# PlacaResistencia_VFinal.net
KiCad netlist of a schematic drawn in EAGLE
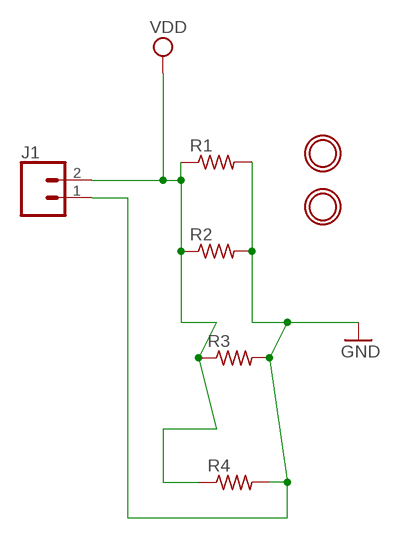
[diagram p0: schematic, sheet 1]

(export (version "E")
  (design (tool "Eeschema 10.0.6"))
  (components
    (comp (ref "GND")
      (value "MOUNTINGHOLE2.5")
      (footprint "eagle-import:MOUNTINGHOLE_2.5_PLATED")
      (libsource (lib "eagle-import") (part "MOUNTINGHOLE2.5"))
    )
    (comp (ref "GND2")
      (value "MOUNTINGHOLE2.5")
      (footprint "eagle-import:MOUNTINGHOLE_2.5_PLATED")
      (libsource (lib "eagle-import") (part "MOUNTINGHOLE2.5"))
    )
    (comp (ref "J1")
      (value "CONN_02")
      (footprint "eagle-import:1X02")
      (libsource (lib "eagle-import") (part "CONN_02"))
    )
    (comp (ref "R1")
      (value "R-US_R2512")
      (footprint "eagle-import:R2512")
      (libsource (lib "eagle-import") (part "R-US_R2512"))
    )
    (comp (ref "R2")
      (value "R-US_R2512")
      (footprint "eagle-import:R2512")
      (libsource (lib "eagle-import") (part "R-US_R2512"))
    )
    (comp (ref "R3")
      (value "R-US_R2512")
      (footprint "eagle-import:R2512")
      (libsource (lib "eagle-import") (part "R-US_R2512"))
    )
    (comp (ref "R4")
      (value "R-US_R2512")
      (footprint "eagle-import:R2512")
      (libsource (lib "eagle-import") (part "R-US_R2512"))
    )
  )
  (nets
    (net (code "1") (name "GND") (class "Default")
      (node (ref "J1") (pin "1") (pinfunction "1_1") (pintype "passive"))
      (node (ref "R1") (pin "2") (pinfunction "2_2") (pintype "passive"))
      (node (ref "R2") (pin "2") (pinfunction "2_2") (pintype "passive"))
      (node (ref "R3") (pin "2") (pinfunction "2_2") (pintype "passive"))
      (node (ref "R4") (pin "2") (pinfunction "2_2") (pintype "passive"))
    )
    (net (code "2") (name "VDD") (class "Default")
      (node (ref "J1") (pin "2") (pinfunction "2_2") (pintype "passive"))
      (node (ref "R1") (pin "1") (pinfunction "1_1") (pintype "passive"))
      (node (ref "R2") (pin "1") (pinfunction "1_1") (pintype "passive"))
      (node (ref "R3") (pin "1") (pinfunction "1_1") (pintype "passive"))
      (node (ref "R4") (pin "1") (pinfunction "1_1") (pintype "passive"))
    )
  )
)
